# Regulators.net
KiCad netlist of a schematic drawn in EAGLE
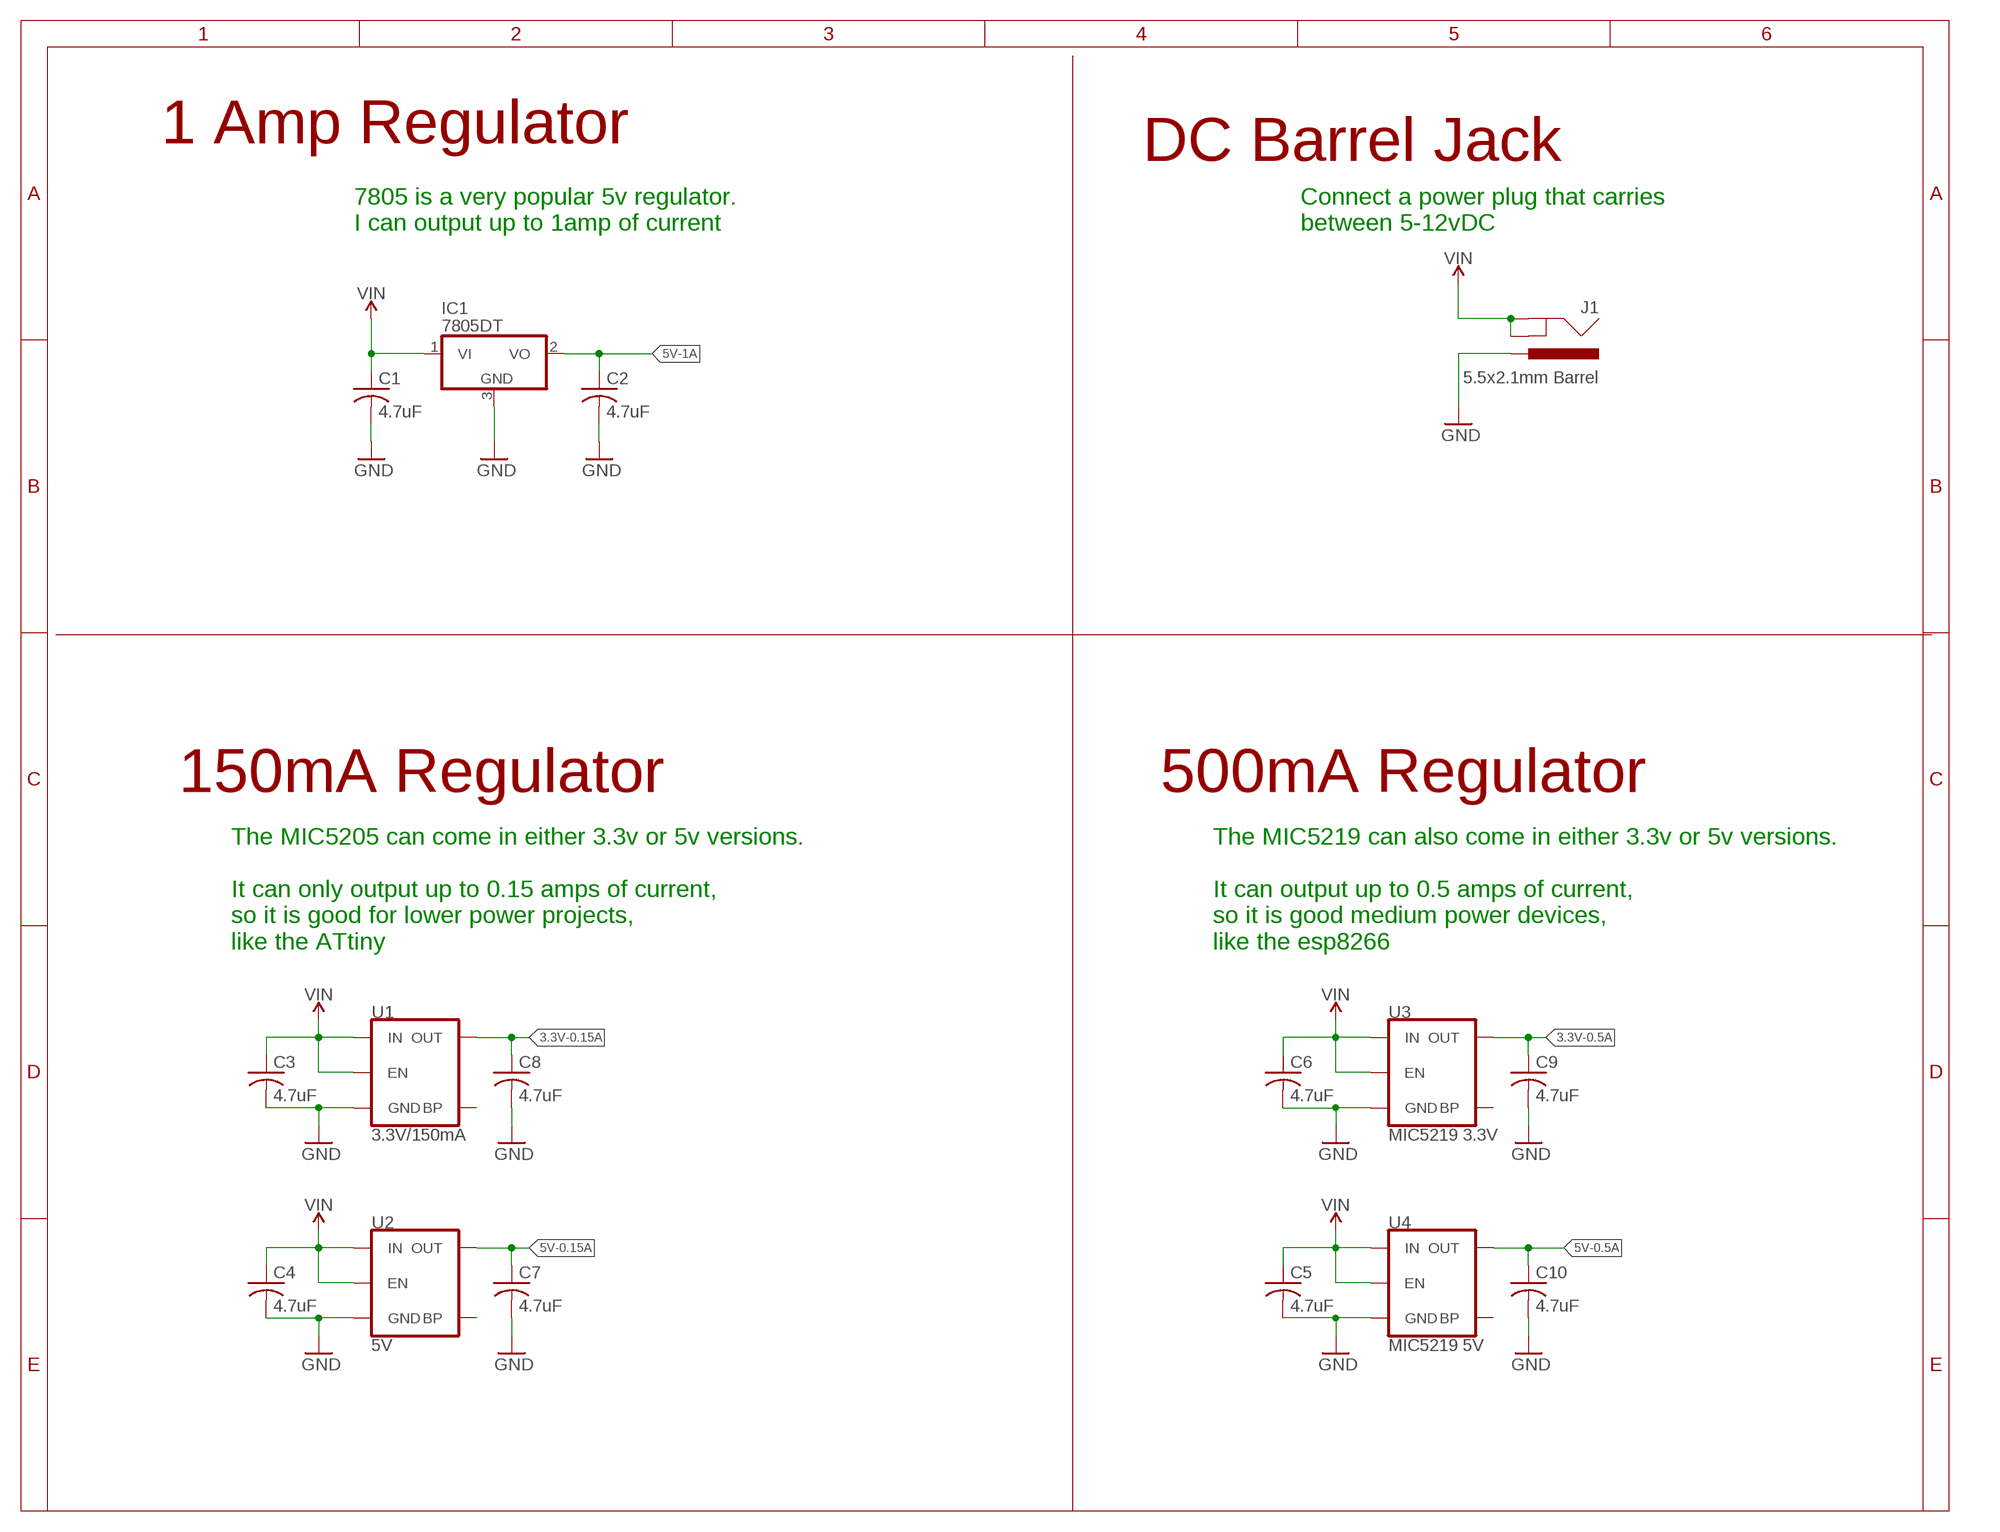
[diagram p0: schematic, sheet 1]

(export (version "E")
  (design (tool "Eeschema 10.0.6"))
  (components
    (comp (ref "C1")
      (value "4.7uF")
      (footprint "eagle-import:C0603")
      (libsource (lib "eagle-import") (part "C-USC0603"))
    )
    (comp (ref "C2")
      (value "4.7uF")
      (footprint "eagle-import:C0603")
      (libsource (lib "eagle-import") (part "C-USC0603"))
    )
    (comp (ref "C3")
      (value "4.7uF")
      (footprint "eagle-import:C0603")
      (libsource (lib "eagle-import") (part "C-USC0603"))
    )
    (comp (ref "C4")
      (value "4.7uF")
      (footprint "eagle-import:C0603")
      (libsource (lib "eagle-import") (part "C-USC0603"))
    )
    (comp (ref "C5")
      (value "4.7uF")
      (footprint "eagle-import:C0603")
      (libsource (lib "eagle-import") (part "C-USC0603"))
    )
    (comp (ref "C6")
      (value "4.7uF")
      (footprint "eagle-import:C0603")
      (libsource (lib "eagle-import") (part "C-USC0603"))
    )
    (comp (ref "C7")
      (value "4.7uF")
      (footprint "eagle-import:C0603")
      (libsource (lib "eagle-import") (part "C-USC0603"))
    )
    (comp (ref "C8")
      (value "4.7uF")
      (footprint "eagle-import:C0603")
      (libsource (lib "eagle-import") (part "C-USC0603"))
    )
    (comp (ref "C9")
      (value "4.7uF")
      (footprint "eagle-import:C0603")
      (libsource (lib "eagle-import") (part "C-USC0603"))
    )
    (comp (ref "C10")
      (value "4.7uF")
      (footprint "eagle-import:C0603")
      (libsource (lib "eagle-import") (part "C-USC0603"))
    )
    (comp (ref "IC1")
      (value "7805DT")
      (footprint "eagle-import:TO252")
      (libsource (lib "eagle-import") (part "78DT05"))
    )
    (comp (ref "J1")
      (value "5.5x2.1mm Barrel")
      (footprint "eagle-import:POWER_JACK_SMD")
      (libsource (lib "eagle-import") (part "POWER_JACKSMD"))
    )
    (comp (ref "U1")
      (value "3.3V/150mA")
      (footprint "eagle-import:SOT23-5")
      (libsource (lib "eagle-import") (part "V_REG_MIC52053.3V"))
    )
    (comp (ref "U2")
      (value "5V")
      (footprint "eagle-import:SOT23-5")
      (libsource (lib "eagle-import") (part "V_REG_MIC52055V"))
    )
    (comp (ref "U3")
      (value "MIC5219 3.3V")
      (footprint "eagle-import:SOT23-5")
      (libsource (lib "eagle-import") (part "V_REG_MIC52193.3V"))
    )
    (comp (ref "U4")
      (value "MIC5219 5V")
      (footprint "eagle-import:SOT23-5")
      (libsource (lib "eagle-import") (part "V_REG_MIC52195V"))
    )
  )
  (nets
    (net (code "1") (name "3.3V-0.5A") (class "Default")
      (node (ref "C9") (pin "1") (pinfunction "1_1") (pintype "passive"))
      (node (ref "U3") (pin "5") (pinfunction "OUT_5") (pintype "passive"))
    )
    (net (code "2") (name "3.3V-0.15A") (class "Default")
      (node (ref "C8") (pin "1") (pinfunction "1_1") (pintype "passive"))
      (node (ref "U1") (pin "5") (pinfunction "OUT_5") (pintype "passive"))
    )
    (net (code "3") (name "5V-0.5A") (class "Default")
      (node (ref "C10") (pin "1") (pinfunction "1_1") (pintype "passive"))
      (node (ref "U4") (pin "5") (pinfunction "OUT_5") (pintype "passive"))
    )
    (net (code "4") (name "5V-0.15A") (class "Default")
      (node (ref "C7") (pin "1") (pinfunction "1_1") (pintype "passive"))
      (node (ref "U2") (pin "5") (pinfunction "OUT_5") (pintype "passive"))
    )
    (net (code "5") (name "5V-1A") (class "Default")
      (node (ref "C2") (pin "1") (pinfunction "1_1") (pintype "passive"))
      (node (ref "IC1") (pin "2") (pinfunction "VO_2") (pintype "passive"))
    )
    (net (code "6") (name "GND") (class "Default")
      (node (ref "C1") (pin "2") (pinfunction "2_2") (pintype "passive"))
      (node (ref "C10") (pin "2") (pinfunction "2_2") (pintype "passive"))
      (node (ref "C2") (pin "2") (pinfunction "2_2") (pintype "passive"))
      (node (ref "C3") (pin "2") (pinfunction "2_2") (pintype "passive"))
      (node (ref "C4") (pin "2") (pinfunction "2_2") (pintype "passive"))
      (node (ref "C5") (pin "2") (pinfunction "2_2") (pintype "passive"))
      (node (ref "C6") (pin "2") (pinfunction "2_2") (pintype "passive"))
      (node (ref "C7") (pin "2") (pinfunction "2_2") (pintype "passive"))
      (node (ref "C8") (pin "2") (pinfunction "2_2") (pintype "passive"))
      (node (ref "C9") (pin "2") (pinfunction "2_2") (pintype "passive"))
      (node (ref "IC1") (pin "3") (pinfunction "GND_3") (pintype "passive"))
      (node (ref "J1") (pin "VIN0") (pinfunction "PWR_VIN0") (pintype "bidirectional"))
      (node (ref "U1") (pin "2") (pinfunction "GND_2") (pintype "input"))
      (node (ref "U2") (pin "2") (pinfunction "GND_2") (pintype "input"))
      (node (ref "U3") (pin "2") (pinfunction "GND_2") (pintype "input"))
      (node (ref "U4") (pin "2") (pinfunction "GND_2") (pintype "input"))
    )
    (net (code "7") (name "VIN") (class "Default")
      (node (ref "C1") (pin "1") (pinfunction "1_1") (pintype "passive"))
      (node (ref "C3") (pin "1") (pinfunction "1_1") (pintype "passive"))
      (node (ref "C4") (pin "1") (pinfunction "1_1") (pintype "passive"))
      (node (ref "C5") (pin "1") (pinfunction "1_1") (pintype "passive"))
      (node (ref "C6") (pin "1") (pinfunction "1_1") (pintype "passive"))
      (node (ref "IC1") (pin "1") (pinfunction "VI_1") (pintype "input"))
      (node (ref "J1") (pin "GND") (pinfunction "GNDBREAK_GND") (pintype "bidirectional"))
      (node (ref "J1") (pin "P$4") (pinfunction "GND_P$4") (pintype "bidirectional"))
      (node (ref "U1") (pin "1") (pinfunction "IN_1") (pintype "input"))
      (node (ref "U1") (pin "3") (pinfunction "EN_3") (pintype "input"))
      (node (ref "U2") (pin "1") (pinfunction "IN_1") (pintype "input"))
      (node (ref "U2") (pin "3") (pinfunction "EN_3") (pintype "input"))
      (node (ref "U3") (pin "1") (pinfunction "IN_1") (pintype "input"))
      (node (ref "U3") (pin "3") (pinfunction "EN_3") (pintype "input"))
      (node (ref "U4") (pin "1") (pinfunction "IN_1") (pintype "input"))
      (node (ref "U4") (pin "3") (pinfunction "EN_3") (pintype "input"))
    )
    (net (code "8") (name "unconnected-(U1-BP-Pad4)") (class "Default")
      (node (ref "U1") (pin "4") (pinfunction "BP_4") (pintype "input"))
    )
    (net (code "9") (name "unconnected-(U2-BP-Pad4)") (class "Default")
      (node (ref "U2") (pin "4") (pinfunction "BP_4") (pintype "input"))
    )
    (net (code "10") (name "unconnected-(U3-BP-Pad4)") (class "Default")
      (node (ref "U3") (pin "4") (pinfunction "BP_4") (pintype "input"))
    )
    (net (code "11") (name "unconnected-(U4-BP-Pad4)") (class "Default")
      (node (ref "U4") (pin "4") (pinfunction "BP_4") (pintype "input"))
    )
  )
)
